# OptodeControl.net
KiCad netlist of a schematic drawn in Altium Designer
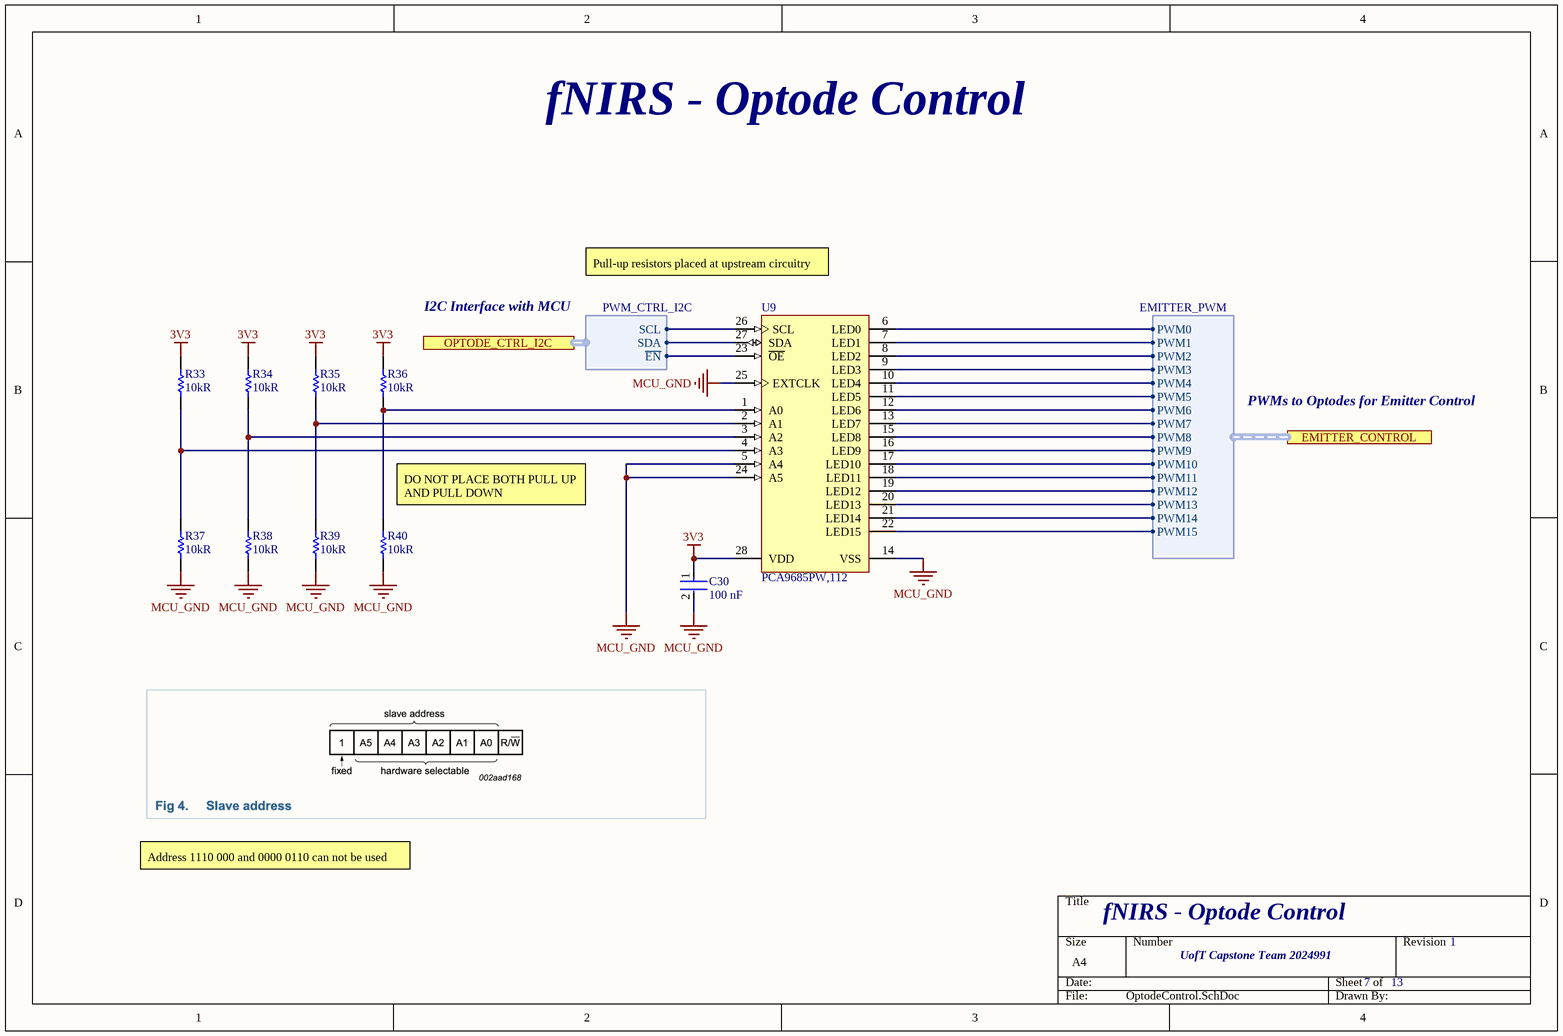
[diagram p0: OptodeControl.SchDoc]

(export (version "E")
  (design (tool "Eeschema 10.0.6"))
  (components
    (comp (ref "C30")
      (value "CC0603KRX7R7BB104")
      (footprint "FP-CC0603-DA-MFG")
      (description "CAP CER 0.1UF 16V X7R 0603")
      (fields
        (field (name "OCTOPART") "https://octopart.com/cc0603krx7r7bb104-yageo-192941")
        (field (name "TOLERANCE") "0.1")
        (field (name "CAPACITANCE") "100 nF")
      )
      (libsource (lib "Altium Content Vault") (part "11868f565c42a9108669ba33697ecf6"))
    )
    (comp (ref "R33")
      (value "CRCW060310K0FKEA")
      (footprint "RESC1609X50X30NL8T20")
      (description "Chip Resistor, 10 KOhm, +/- 1%, 100 mW, -55 to 155 degC, 0603 (1608 Metric), RoHS, Tape and Reel")
      (fields (field (name "MANUFACTURER") "Vishay Semiconductor") (field (name "RESISTANCE") "10kR"))
      (libsource (lib "Altium Content Vault") (part "RES-2"))
    )
    (comp (ref "R34")
      (value "CRCW060310K0FKEA")
      (footprint "RESC1609X50X30NL8T20")
      (description "Chip Resistor, 10 KOhm, +/- 1%, 100 mW, -55 to 155 degC, 0603 (1608 Metric), RoHS, Tape and Reel")
      (fields (field (name "MANUFACTURER") "Vishay Semiconductor") (field (name "RESISTANCE") "10kR"))
      (libsource (lib "Altium Content Vault") (part "RES-2"))
    )
    (comp (ref "R35")
      (value "CRCW060310K0FKEA")
      (footprint "RESC1609X50X30NL8T20")
      (description "Chip Resistor, 10 KOhm, +/- 1%, 100 mW, -55 to 155 degC, 0603 (1608 Metric), RoHS, Tape and Reel")
      (fields (field (name "MANUFACTURER") "Vishay Semiconductor") (field (name "RESISTANCE") "10kR"))
      (libsource (lib "Altium Content Vault") (part "RES-2"))
    )
    (comp (ref "R36")
      (value "CRCW060310K0FKEA")
      (footprint "RESC1609X50X30NL8T20")
      (description "Chip Resistor, 10 KOhm, +/- 1%, 100 mW, -55 to 155 degC, 0603 (1608 Metric), RoHS, Tape and Reel")
      (fields (field (name "MANUFACTURER") "Vishay Semiconductor") (field (name "RESISTANCE") "10kR"))
      (libsource (lib "Altium Content Vault") (part "RES-2"))
    )
    (comp (ref "R37")
      (value "CRCW060310K0FKEA")
      (footprint "RESC1609X50X30NL8T20")
      (description "Chip Resistor, 10 KOhm, +/- 1%, 100 mW, -55 to 155 degC, 0603 (1608 Metric), RoHS, Tape and Reel")
      (fields (field (name "MANUFACTURER") "Vishay Semiconductor") (field (name "RESISTANCE") "10kR"))
      (libsource (lib "Altium Content Vault") (part "RES-2"))
    )
    (comp (ref "R38")
      (value "CRCW060310K0FKEA")
      (footprint "RESC1609X50X30NL8T20")
      (description "Chip Resistor, 10 KOhm, +/- 1%, 100 mW, -55 to 155 degC, 0603 (1608 Metric), RoHS, Tape and Reel")
      (fields (field (name "MANUFACTURER") "Vishay Semiconductor") (field (name "RESISTANCE") "10kR"))
      (libsource (lib "Altium Content Vault") (part "RES-2"))
    )
    (comp (ref "R39")
      (value "CRCW060310K0FKEA")
      (footprint "RESC1609X50X30NL8T20")
      (description "Chip Resistor, 10 KOhm, +/- 1%, 100 mW, -55 to 155 degC, 0603 (1608 Metric), RoHS, Tape and Reel")
      (fields (field (name "MANUFACTURER") "Vishay Semiconductor") (field (name "RESISTANCE") "10kR"))
      (libsource (lib "Altium Content Vault") (part "RES-2"))
    )
    (comp (ref "R40")
      (value "CRCW060310K0FKEA")
      (footprint "RESC1609X50X30NL8T20")
      (description "Chip Resistor, 10 KOhm, +/- 1%, 100 mW, -55 to 155 degC, 0603 (1608 Metric), RoHS, Tape and Reel")
      (fields (field (name "MANUFACTURER") "Vishay Semiconductor") (field (name "RESISTANCE") "10kR"))
      (libsource (lib "Altium Content Vault") (part "RES-2"))
    )
    (comp (ref "U9")
      (value "PCA9685PW,112")
      (footprint "SOT361-1_V")
      (fields (field (name "PARTNUMBER") "PCA9685"))
      (libsource (lib "Altium Content Vault") (part "NXP-PCA9685-SOT361-1"))
    )
  )
  (nets
    (net (code "3") (name "/PWM0") (class "Default")
      (node (ref "U9") (pin "6") (pinfunction "LED0_6") (pintype "tri_state"))
    )
    (net (code "4") (name "/PWM1") (class "Default")
      (node (ref "U9") (pin "7") (pinfunction "LED1_7") (pintype "tri_state"))
    )
    (net (code "5") (name "/PWM2") (class "Default")
      (node (ref "U9") (pin "8") (pinfunction "LED2_8") (pintype "tri_state"))
    )
    (net (code "6") (name "/PWM3") (class "Default")
      (node (ref "U9") (pin "9") (pinfunction "LED3_9") (pintype "tri_state"))
    )
    (net (code "7") (name "/PWM4") (class "Default")
      (node (ref "U9") (pin "10") (pinfunction "LED4_10") (pintype "tri_state"))
    )
    (net (code "8") (name "/PWM5") (class "Default")
      (node (ref "U9") (pin "11") (pinfunction "LED5_11") (pintype "tri_state"))
    )
    (net (code "9") (name "/PWM6") (class "Default")
      (node (ref "U9") (pin "12") (pinfunction "LED6_12") (pintype "tri_state"))
    )
    (net (code "10") (name "/PWM7") (class "Default")
      (node (ref "U9") (pin "13") (pinfunction "LED7_13") (pintype "tri_state"))
    )
    (net (code "11") (name "/PWM8") (class "Default")
      (node (ref "U9") (pin "15") (pinfunction "LED8_15") (pintype "tri_state"))
    )
    (net (code "12") (name "/PWM9") (class "Default")
      (node (ref "U9") (pin "16") (pinfunction "LED9_16") (pintype "tri_state"))
    )
    (net (code "13") (name "/PWM10") (class "Default")
      (node (ref "U9") (pin "17") (pinfunction "LED10_17") (pintype "tri_state"))
    )
    (net (code "14") (name "/PWM11") (class "Default")
      (node (ref "U9") (pin "18") (pinfunction "LED11_18") (pintype "tri_state"))
    )
    (net (code "15") (name "/PWM12") (class "Default")
      (node (ref "U9") (pin "19") (pinfunction "LED12_19") (pintype "tri_state"))
    )
    (net (code "16") (name "/PWM13") (class "Default")
      (node (ref "U9") (pin "20") (pinfunction "LED13_20") (pintype "tri_state"))
    )
    (net (code "17") (name "/PWM14") (class "Default")
      (node (ref "U9") (pin "21") (pinfunction "LED14_21") (pintype "tri_state"))
    )
    (net (code "18") (name "/PWM15") (class "Default")
      (node (ref "U9") (pin "22") (pinfunction "LED15_22") (pintype "tri_state"))
    )
    (net (code "19") (name "/SCL") (class "Default")
      (node (ref "U9") (pin "26") (pinfunction "SCL_26") (pintype "input"))
    )
    (net (code "20") (name "/SDA") (class "Default")
      (node (ref "U9") (pin "27") (pinfunction "SDA_27") (pintype "bidirectional"))
    )
    (net (code "23") (name "/~{EN}") (class "Default")
      (node (ref "U9") (pin "23") (pinfunction "~{OE}_23") (pintype "input"))
    )
    (net (code "24") (name "3V3") (class "Default")
      (node (ref "C30") (pin "1") (pinfunction "1_1") (pintype "passive"))
      (node (ref "R33") (pin "2") (pinfunction "2_2") (pintype "passive"))
      (node (ref "R34") (pin "2") (pinfunction "2_2") (pintype "passive"))
      (node (ref "R35") (pin "2") (pinfunction "2_2") (pintype "passive"))
      (node (ref "R36") (pin "2") (pinfunction "2_2") (pintype "passive"))
      (node (ref "U9") (pin "28") (pinfunction "VDD_28") (pintype "power_in"))
    )
    (net (code "25") (name "MCU_GND") (class "Default")
      (node (ref "C30") (pin "2") (pinfunction "2_2") (pintype "passive"))
      (node (ref "R37") (pin "1") (pinfunction "1_1") (pintype "passive"))
      (node (ref "R38") (pin "1") (pinfunction "1_1") (pintype "passive"))
      (node (ref "R39") (pin "1") (pinfunction "1_1") (pintype "passive"))
      (node (ref "R40") (pin "1") (pinfunction "1_1") (pintype "passive"))
      (node (ref "U9") (pin "14") (pinfunction "VSS_14") (pintype "power_in"))
      (node (ref "U9") (pin "24") (pinfunction "A5_24") (pintype "input"))
      (node (ref "U9") (pin "25") (pinfunction "EXTCLK_25") (pintype "input"))
      (node (ref "U9") (pin "5") (pinfunction "A4_5") (pintype "input"))
    )
    (net (code "26") (name "Net-(U9-A0)") (class "Default")
      (node (ref "R36") (pin "1") (pinfunction "1_1") (pintype "passive"))
      (node (ref "R40") (pin "2") (pinfunction "2_2") (pintype "passive"))
      (node (ref "U9") (pin "1") (pinfunction "A0_1") (pintype "input"))
    )
    (net (code "27") (name "Net-(U9-A1)") (class "Default")
      (node (ref "R35") (pin "1") (pinfunction "1_1") (pintype "passive"))
      (node (ref "R39") (pin "2") (pinfunction "2_2") (pintype "passive"))
      (node (ref "U9") (pin "2") (pinfunction "A1_2") (pintype "input"))
    )
    (net (code "28") (name "Net-(U9-A2)") (class "Default")
      (node (ref "R34") (pin "1") (pinfunction "1_1") (pintype "passive"))
      (node (ref "R38") (pin "2") (pinfunction "2_2") (pintype "passive"))
      (node (ref "U9") (pin "3") (pinfunction "A2_3") (pintype "input"))
    )
    (net (code "29") (name "Net-(U9-A3)") (class "Default")
      (node (ref "R33") (pin "1") (pinfunction "1_1") (pintype "passive"))
      (node (ref "R37") (pin "2") (pinfunction "2_2") (pintype "passive"))
      (node (ref "U9") (pin "4") (pinfunction "A3_4") (pintype "input"))
    )
  )
)
